# TBA820-Amplifier-Stripboard.net
KiCad netlist of a schematic drawn in EAGLE
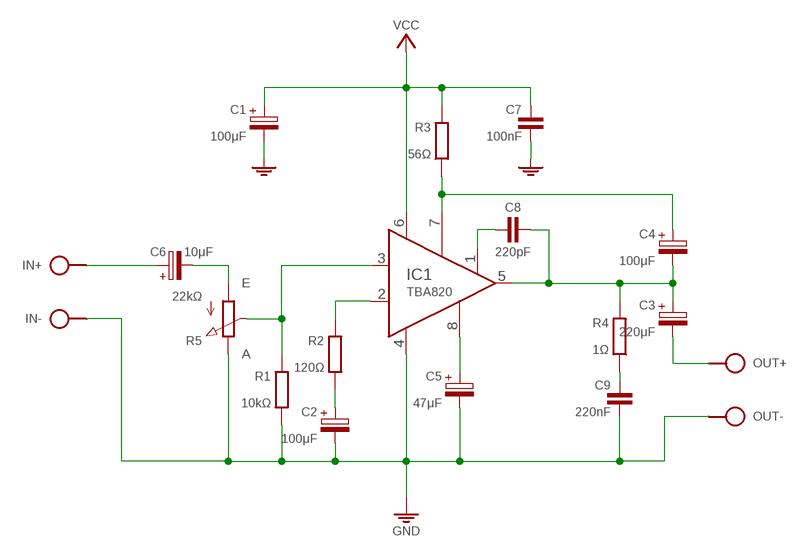
[diagram p0: schematic, sheet 1]

(export (version "E")
  (design (tool "Eeschema 10.0.6"))
  (components
    (comp (ref "C1")
      (value "100μF")
      (footprint "eagle-import:E2.5-4_V")
      (libsource (lib "eagle-import") (part "CPOLE2,5-4/V"))
    )
    (comp (ref "C2")
      (value "100μF")
      (footprint "eagle-import:E2.5-4_V")
      (libsource (lib "eagle-import") (part "CPOLE2,5-4/V"))
    )
    (comp (ref "C3")
      (value "220μF")
      (footprint "eagle-import:E2,5-5")
      (libsource (lib "eagle-import") (part "CPOLE2.5-5"))
    )
    (comp (ref "C4")
      (value "100μF")
      (footprint "eagle-import:E5-4")
      (libsource (lib "eagle-import") (part "CPOLE5-4"))
    )
    (comp (ref "C5")
      (value "47μF")
      (footprint "eagle-import:E2,5-3")
      (libsource (lib "eagle-import") (part "CPOLE2,5-3"))
    )
    (comp (ref "C6")
      (value "10μF")
      (footprint "eagle-import:E2,5-3")
      (libsource (lib "eagle-import") (part "CPOL-HE2,5-3"))
    )
    (comp (ref "C7")
      (value "100nF")
      (footprint "eagle-import:C025-024X044")
      (libsource (lib "eagle-import") (part "C025-024X044"))
    )
    (comp (ref "C8")
      (value "220pF")
      (footprint "eagle-import:C050-024X044_V")
      (libsource (lib "eagle-import") (part "C-H050-024X044/V"))
    )
    (comp (ref "C9")
      (value "220nF")
      (footprint "eagle-import:C075-020X044")
      (libsource (lib "eagle-import") (part "C075-020X044"))
    )
    (comp (ref "IC1")
      (value "TBA820")
      (footprint "eagle-import:DIL08")
      (libsource (lib "eagle-import") (part "TBA820"))
    )
    (comp (ref "IN")
      (value "SPAD+--+")
      (footprint "eagle-import:SPAD-+")
      (libsource (lib "eagle-import") (part "SPAD+--+"))
    )
    (comp (ref "OUT")
      (value "SPAD+-+-")
      (footprint "eagle-import:SPAD+-")
      (libsource (lib "eagle-import") (part "SPAD+-+-"))
    )
    (comp (ref "R1")
      (value "10kΩ")
      (footprint "eagle-import:0202_2V")
      (libsource (lib "eagle-import") (part "R0202/2V"))
    )
    (comp (ref "R2")
      (value "120Ω")
      (footprint "eagle-import:0204_10-V")
      (libsource (lib "eagle-import") (part "R0204/10-V"))
    )
    (comp (ref "R3")
      (value "56Ω")
      (footprint "eagle-import:0202_2V")
      (libsource (lib "eagle-import") (part "R0202/2V"))
    )
    (comp (ref "R4")
      (value "1Ω")
      (footprint "eagle-import:0204_10-V")
      (libsource (lib "eagle-import") (part "R0204/10-V"))
    )
    (comp (ref "R5")
      (value "22kΩ")
      (footprint "eagle-import:CONN-3P")
      (libsource (lib "eagle-import") (part "POT-3P"))
    )
    (comp (ref "S4")
      (value "VCC_GNDPWR-R")
      (footprint "eagle-import:PWR-R")
      (libsource (lib "eagle-import") (part "VCC_GNDPWR-R"))
    )
  )
  (nets
    (net (code "1") (name "GND") (class "Default")
      (node (ref "C1") (pin "-") (pinfunction "-_-") (pintype "passive"))
      (node (ref "C2") (pin "-") (pinfunction "-_-") (pintype "passive"))
      (node (ref "C5") (pin "-") (pinfunction "-_-") (pintype "passive"))
      (node (ref "C7") (pin "2") (pinfunction "2_2") (pintype "passive"))
      (node (ref "C9") (pin "2") (pinfunction "2_2") (pintype "passive"))
      (node (ref "IC1") (pin "4") (pinfunction "GND_4") (pintype "power_in"))
      (node (ref "IN") (pin "1") (pinfunction "P$1_1") (pintype "passive"))
      (node (ref "OUT") (pin "1") (pinfunction "P$1_1") (pintype "passive"))
      (node (ref "R1") (pin "2") (pinfunction "1_2") (pintype "passive"))
      (node (ref "R5") (pin "3") (pinfunction "E_3") (pintype "passive"))
      (node (ref "S4") (pin "1") (pinfunction "GND_1") (pintype "power_in"))
    )
    (net (code "2") (name "Net-(IC1-BOOT)") (class "Default")
      (node (ref "C4") (pin "+") (pinfunction "+_+") (pintype "passive"))
      (node (ref "IC1") (pin "7") (pinfunction "BOOT_7") (pintype "input"))
      (node (ref "R3") (pin "2") (pinfunction "1_2") (pintype "passive"))
    )
    (net (code "3") (name "Net-(IC1-FREQ)") (class "Default")
      (node (ref "C8") (pin "1") (pinfunction "1_1") (pintype "passive"))
      (node (ref "IC1") (pin "1") (pinfunction "FREQ_1") (pintype "input"))
    )
    (net (code "4") (name "Net-(IC1-GAIN)") (class "Default")
      (node (ref "IC1") (pin "2") (pinfunction "GAIN_2") (pintype "input"))
      (node (ref "R2") (pin "1") (pinfunction "2_1") (pintype "passive"))
    )
    (net (code "5") (name "Net-(IC1-INPUT)") (class "Default")
      (node (ref "IC1") (pin "3") (pinfunction "INPUT_3") (pintype "input"))
      (node (ref "R1") (pin "1") (pinfunction "2_1") (pintype "passive"))
      (node (ref "R5") (pin "2") (pinfunction "S_2") (pintype "passive"))
    )
    (net (code "6") (name "Net-(IC1-OUT)") (class "Default")
      (node (ref "C3") (pin "+") (pinfunction "+_+") (pintype "passive"))
      (node (ref "C4") (pin "-") (pinfunction "-_-") (pintype "passive"))
      (node (ref "C8") (pin "2") (pinfunction "2_2") (pintype "passive"))
      (node (ref "IC1") (pin "5") (pinfunction "OUT_5") (pintype "output"))
      (node (ref "R4") (pin "1") (pinfunction "2_1") (pintype "passive"))
    )
    (net (code "7") (name "Net-(IC1-RIPPLE)") (class "Default")
      (node (ref "C5") (pin "+") (pinfunction "+_+") (pintype "passive"))
      (node (ref "IC1") (pin "8") (pinfunction "RIPPLE_8") (pintype "input"))
    )
    (net (code "8") (name "Net-(IC1-VCC)") (class "Default")
      (node (ref "C1") (pin "+") (pinfunction "+_+") (pintype "passive"))
      (node (ref "C7") (pin "1") (pinfunction "1_1") (pintype "passive"))
      (node (ref "IC1") (pin "6") (pinfunction "VCC_6") (pintype "power_in"))
      (node (ref "R3") (pin "1") (pinfunction "2_1") (pintype "passive"))
      (node (ref "S4") (pin "2") (pinfunction "VCC_2") (pintype "power_in"))
    )
    (net (code "9") (name "Net-(INA-P$1)") (class "Default")
      (node (ref "C6") (pin "+") (pinfunction "+_+") (pintype "passive"))
      (node (ref "IN") (pin "2") (pinfunction "P$1_2") (pintype "passive"))
    )
    (net (code "10") (name "Net-(OUTA-P$1)") (class "Default")
      (node (ref "C3") (pin "-") (pinfunction "-_-") (pintype "passive"))
      (node (ref "OUT") (pin "2") (pinfunction "P$1_2") (pintype "passive"))
    )
    (net (code "11") (name "Net-(R2-1)") (class "Default")
      (node (ref "C2") (pin "+") (pinfunction "+_+") (pintype "passive"))
      (node (ref "R2") (pin "2") (pinfunction "1_2") (pintype "passive"))
    )
    (net (code "12") (name "Net-(R4-1)") (class "Default")
      (node (ref "C9") (pin "1") (pinfunction "1_1") (pintype "passive"))
      (node (ref "R4") (pin "2") (pinfunction "1_2") (pintype "passive"))
    )
    (net (code "13") (name "Net-(R5-A)") (class "Default")
      (node (ref "C6") (pin "-") (pinfunction "-_-") (pintype "passive"))
      (node (ref "R5") (pin "1") (pinfunction "A_1") (pintype "passive"))
    )
  )
)
